# Telecomanda_Licenta.net
KiCad netlist of a schematic drawn in EAGLE
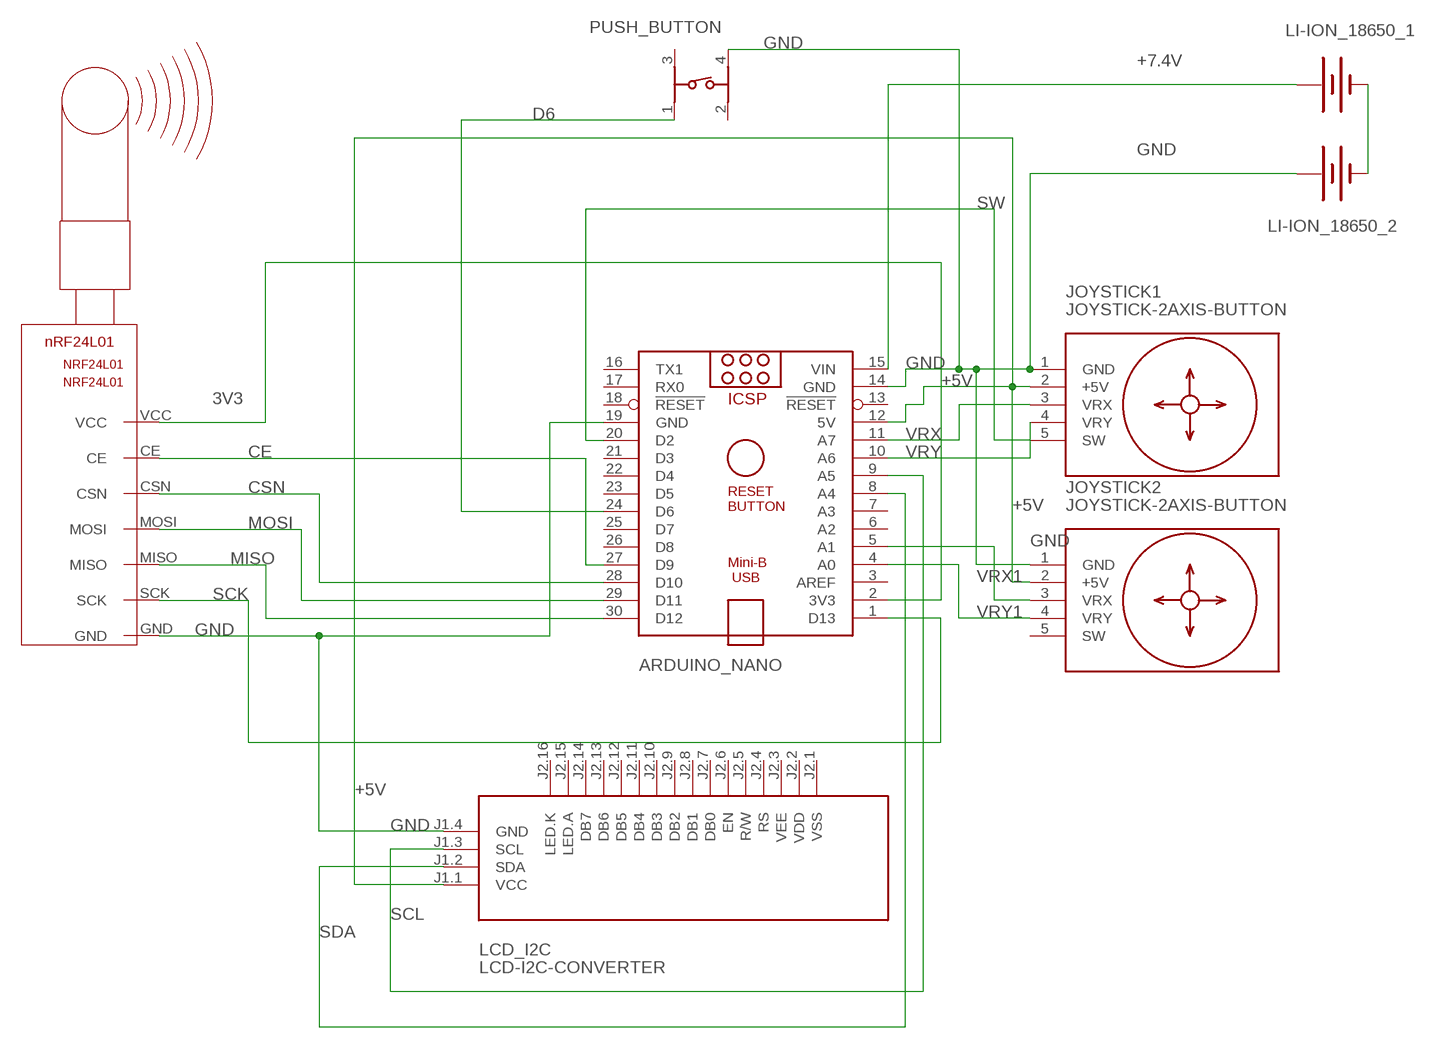
[diagram p0: schematic, sheet 1]

(export (version "E")
  (design (tool "Eeschema 10.0.6"))
  (components
    (comp (ref "ARDUINO_NANO")
      (value "ARDUINO_NANO")
      (footprint "eagle-import:ARDUINO_NANO")
      (libsource (lib "eagle-import") (part "ARDUINO_NANO"))
    )
    (comp (ref "JOYSTICK1")
      (value "JOYSTICK-2AXIS-BUTTON")
      (footprint "eagle-import:JOYSTICK-2AXIS-BUTTON")
      (libsource (lib "eagle-import") (part "JOYSTICK-2AXIS-BUTTON"))
    )
    (comp (ref "JOYSTICK2")
      (value "JOYSTICK-2AXIS-BUTTON")
      (footprint "eagle-import:JOYSTICK-2AXIS-BUTTON")
      (libsource (lib "eagle-import") (part "JOYSTICK-2AXIS-BUTTON"))
    )
    (comp (ref "LCD_I2C")
      (value "LCD-I2C-CONVERTER")
      (footprint "eagle-import:LCD-I2C-CONVERTER")
      (libsource (lib "eagle-import") (part "LCD-I2C-CONVERTER"))
    )
    (comp (ref "LI-ION_18650_1")
      (value "BATTERY-18650")
      (footprint "eagle-import:BATTERY_18650-HOLDER")
      (libsource (lib "eagle-import") (part "BATTERY-18650"))
    )
    (comp (ref "LI-ION_18650_2")
      (value "BATTERY-18650")
      (footprint "eagle-import:BATTERY_18650-HOLDER")
      (libsource (lib "eagle-import") (part "BATTERY-18650"))
    )
    (comp (ref "NRF24L01")
      (value "NRF24L01")
      (footprint "eagle-import:NRF24L01")
      (libsource (lib "eagle-import") (part "NRF24L01"))
    )
    (comp (ref "PUSH_BUTTON")
      (value "430152050836")
      (footprint "eagle-import:430152050836")
      (libsource (lib "eagle-import") (part "430152050836"))
    )
  )
  (nets
    (net (code "1") (name "/+5V") (class "Default")
      (node (ref "ARDUINO_NANO") (pin "12") (pinfunction "5V_12") (pintype "power_in"))
      (node (ref "JOYSTICK1") (pin "2") (pinfunction "+5V_2") (pintype "power_in"))
      (node (ref "JOYSTICK2") (pin "2") (pinfunction "+5V_2") (pintype "power_in"))
      (node (ref "LCD_I2C") (pin "J1.1") (pinfunction "VCC_J1.1") (pintype "power_in"))
    )
    (net (code "2") (name "/+7.4V") (class "Default")
      (node (ref "ARDUINO_NANO") (pin "15") (pinfunction "VIN_15") (pintype "power_in"))
      (node (ref "LI-ION_18650_1") (pin "PWR@1") (pinfunction "+_PWR@1") (pintype "power_in"))
    )
    (net (code "3") (name "/3V3") (class "Default")
      (node (ref "ARDUINO_NANO") (pin "2") (pinfunction "3V3_2") (pintype "output"))
      (node (ref "NRF24L01") (pin "VCC") (pinfunction "VCC_VCC") (pintype "bidirectional"))
    )
    (net (code "4") (name "/CE") (class "Default")
      (node (ref "ARDUINO_NANO") (pin "27") (pinfunction "D9_27") (pintype "bidirectional"))
      (node (ref "NRF24L01") (pin "CE") (pinfunction "CE_CE") (pintype "bidirectional"))
    )
    (net (code "5") (name "/CSN") (class "Default")
      (node (ref "ARDUINO_NANO") (pin "28") (pinfunction "D10_28") (pintype "bidirectional"))
      (node (ref "NRF24L01") (pin "CSN") (pinfunction "CSN_CSN") (pintype "bidirectional"))
    )
    (net (code "6") (name "/D6") (class "Default")
      (node (ref "ARDUINO_NANO") (pin "24") (pinfunction "D6_24") (pintype "bidirectional"))
      (node (ref "PUSH_BUTTON") (pin "1") (pinfunction "1_1") (pintype "passive"))
    )
    (net (code "7") (name "/GND") (class "Default")
      (node (ref "ARDUINO_NANO") (pin "14") (pinfunction "GND_14") (pintype "power_in"))
      (node (ref "ARDUINO_NANO") (pin "19") (pinfunction "GND_19") (pintype "power_in"))
      (node (ref "JOYSTICK1") (pin "1") (pinfunction "GND_1") (pintype "power_in"))
      (node (ref "JOYSTICK2") (pin "1") (pinfunction "GND_1") (pintype "power_in"))
      (node (ref "LCD_I2C") (pin "J1.4") (pinfunction "GND_J1.4") (pintype "power_in"))
      (node (ref "LI-ION_18650_2") (pin "PWR@1") (pinfunction "+_PWR@1") (pintype "power_in"))
      (node (ref "NRF24L01") (pin "GND") (pinfunction "GND_GND") (pintype "bidirectional"))
      (node (ref "PUSH_BUTTON") (pin "4") (pinfunction "4_4") (pintype "passive"))
    )
    (net (code "8") (name "/MISO") (class "Default")
      (node (ref "ARDUINO_NANO") (pin "30") (pinfunction "D12_30") (pintype "bidirectional"))
      (node (ref "NRF24L01") (pin "MISO") (pinfunction "MISO_MISO") (pintype "bidirectional"))
    )
    (net (code "9") (name "/MOSI") (class "Default")
      (node (ref "ARDUINO_NANO") (pin "29") (pinfunction "D11_29") (pintype "bidirectional"))
      (node (ref "NRF24L01") (pin "MOSI") (pinfunction "MOSI_MOSI") (pintype "bidirectional"))
    )
    (net (code "10") (name "/SCK") (class "Default")
      (node (ref "ARDUINO_NANO") (pin "1") (pinfunction "D13_1") (pintype "bidirectional"))
      (node (ref "NRF24L01") (pin "SCK") (pinfunction "SCK_SCK") (pintype "bidirectional"))
    )
    (net (code "11") (name "/SCL") (class "Default")
      (node (ref "ARDUINO_NANO") (pin "9") (pinfunction "A5_9") (pintype "bidirectional"))
      (node (ref "LCD_I2C") (pin "J1.3") (pinfunction "SCL_J1.3") (pintype "bidirectional"))
    )
    (net (code "12") (name "/SDA") (class "Default")
      (node (ref "ARDUINO_NANO") (pin "8") (pinfunction "A4_8") (pintype "bidirectional"))
      (node (ref "LCD_I2C") (pin "J1.2") (pinfunction "SDA_J1.2") (pintype "bidirectional"))
    )
    (net (code "13") (name "/SW") (class "Default")
      (node (ref "ARDUINO_NANO") (pin "20") (pinfunction "D2_20") (pintype "bidirectional"))
      (node (ref "JOYSTICK1") (pin "5") (pinfunction "SW_5") (pintype "passive"))
    )
    (net (code "14") (name "/VRX") (class "Default")
      (node (ref "ARDUINO_NANO") (pin "11") (pinfunction "A7_11") (pintype "bidirectional"))
      (node (ref "JOYSTICK1") (pin "3") (pinfunction "VRX_3") (pintype "passive"))
    )
    (net (code "15") (name "/VRX1") (class "Default")
      (node (ref "ARDUINO_NANO") (pin "5") (pinfunction "A1_5") (pintype "bidirectional"))
      (node (ref "JOYSTICK2") (pin "3") (pinfunction "VRX_3") (pintype "passive"))
    )
    (net (code "16") (name "/VRY") (class "Default")
      (node (ref "ARDUINO_NANO") (pin "10") (pinfunction "A6_10") (pintype "bidirectional"))
      (node (ref "JOYSTICK1") (pin "4") (pinfunction "VRY_4") (pintype "passive"))
    )
    (net (code "17") (name "/VRY1") (class "Default")
      (node (ref "ARDUINO_NANO") (pin "4") (pinfunction "A0_4") (pintype "bidirectional"))
      (node (ref "JOYSTICK2") (pin "4") (pinfunction "VRY_4") (pintype "passive"))
    )
    (net (code "18") (name "Net-(LI-ION_18650_1--)") (class "Default")
      (node (ref "LI-ION_18650_1") (pin "GND@1") (pinfunction "-_GND@1") (pintype "power_in"))
      (node (ref "LI-ION_18650_2") (pin "GND@1") (pinfunction "-_GND@1") (pintype "power_in"))
    )
    (net (code "19") (name "unconnected-(ARDUINO_NANO-A2-Pad6)") (class "Default")
      (node (ref "ARDUINO_NANO") (pin "6") (pinfunction "A2_6") (pintype "bidirectional"))
    )
    (net (code "20") (name "unconnected-(ARDUINO_NANO-A3-Pad7)") (class "Default")
      (node (ref "ARDUINO_NANO") (pin "7") (pinfunction "A3_7") (pintype "bidirectional"))
    )
    (net (code "21") (name "unconnected-(ARDUINO_NANO-AREF-Pad3)") (class "Default")
      (node (ref "ARDUINO_NANO") (pin "3") (pinfunction "AREF_3") (pintype "input"))
    )
    (net (code "22") (name "unconnected-(ARDUINO_NANO-D3-Pad21)") (class "Default")
      (node (ref "ARDUINO_NANO") (pin "21") (pinfunction "D3_21") (pintype "bidirectional"))
    )
    (net (code "23") (name "unconnected-(ARDUINO_NANO-D4-Pad22)") (class "Default")
      (node (ref "ARDUINO_NANO") (pin "22") (pinfunction "D4_22") (pintype "bidirectional"))
    )
    (net (code "24") (name "unconnected-(ARDUINO_NANO-D5-Pad23)") (class "Default")
      (node (ref "ARDUINO_NANO") (pin "23") (pinfunction "D5_23") (pintype "bidirectional"))
    )
    (net (code "25") (name "unconnected-(ARDUINO_NANO-D7-Pad25)") (class "Default")
      (node (ref "ARDUINO_NANO") (pin "25") (pinfunction "D7_25") (pintype "bidirectional"))
    )
    (net (code "26") (name "unconnected-(ARDUINO_NANO-D8-Pad26)") (class "Default")
      (node (ref "ARDUINO_NANO") (pin "26") (pinfunction "D8_26") (pintype "bidirectional"))
    )
    (net (code "27") (name "unconnected-(ARDUINO_NANO-RX0-Pad17)") (class "Default")
      (node (ref "ARDUINO_NANO") (pin "17") (pinfunction "RX0_17") (pintype "bidirectional"))
    )
    (net (code "28") (name "unconnected-(ARDUINO_NANO-TX1-Pad16)") (class "Default")
      (node (ref "ARDUINO_NANO") (pin "16") (pinfunction "TX1_16") (pintype "bidirectional"))
    )
    (net (code "29") (name "unconnected-(ARDUINO_NANO-~{RESET}-Pad13)") (class "Default")
      (node (ref "ARDUINO_NANO") (pin "13") (pinfunction "~{RESET}_13") (pintype "input"))
    )
    (net (code "30") (name "unconnected-(ARDUINO_NANO-~{RESET}-Pad18)") (class "Default")
      (node (ref "ARDUINO_NANO") (pin "18") (pinfunction "~{RESET}_18") (pintype "input"))
    )
    (net (code "31") (name "unconnected-(JOYSTICK2-SW-Pad5)") (class "Default")
      (node (ref "JOYSTICK2") (pin "5") (pinfunction "SW_5") (pintype "passive"))
    )
    (net (code "32") (name "unconnected-(LCD_I2C-DB0-PadJ2.7)") (class "Default")
      (node (ref "LCD_I2C") (pin "J2.7") (pinfunction "DB0_J2.7") (pintype "bidirectional"))
    )
    (net (code "33") (name "unconnected-(LCD_I2C-DB1-PadJ2.8)") (class "Default")
      (node (ref "LCD_I2C") (pin "J2.8") (pinfunction "DB1_J2.8") (pintype "bidirectional"))
    )
    (net (code "34") (name "unconnected-(LCD_I2C-DB2-PadJ2.9)") (class "Default")
      (node (ref "LCD_I2C") (pin "J2.9") (pinfunction "DB2_J2.9") (pintype "bidirectional"))
    )
    (net (code "35") (name "unconnected-(LCD_I2C-DB3-PadJ2.10)") (class "Default")
      (node (ref "LCD_I2C") (pin "J2.10") (pinfunction "DB3_J2.10") (pintype "bidirectional"))
    )
    (net (code "36") (name "unconnected-(LCD_I2C-DB4-PadJ2.11)") (class "Default")
      (node (ref "LCD_I2C") (pin "J2.11") (pinfunction "DB4_J2.11") (pintype "bidirectional"))
    )
    (net (code "37") (name "unconnected-(LCD_I2C-DB5-PadJ2.12)") (class "Default")
      (node (ref "LCD_I2C") (pin "J2.12") (pinfunction "DB5_J2.12") (pintype "bidirectional"))
    )
    (net (code "38") (name "unconnected-(LCD_I2C-DB6-PadJ2.13)") (class "Default")
      (node (ref "LCD_I2C") (pin "J2.13") (pinfunction "DB6_J2.13") (pintype "bidirectional"))
    )
    (net (code "39") (name "unconnected-(LCD_I2C-DB7-PadJ2.14)") (class "Default")
      (node (ref "LCD_I2C") (pin "J2.14") (pinfunction "DB7_J2.14") (pintype "bidirectional"))
    )
    (net (code "40") (name "unconnected-(LCD_I2C-EN-PadJ2.6)") (class "Default")
      (node (ref "LCD_I2C") (pin "J2.6") (pinfunction "EN_J2.6") (pintype "bidirectional"))
    )
    (net (code "41") (name "unconnected-(LCD_I2C-LED.A-PadJ2.15)") (class "Default")
      (node (ref "LCD_I2C") (pin "J2.15") (pinfunction "LED.A_J2.15") (pintype "bidirectional"))
    )
    (net (code "42") (name "unconnected-(LCD_I2C-LED.K-PadJ2.16)") (class "Default")
      (node (ref "LCD_I2C") (pin "J2.16") (pinfunction "LED.K_J2.16") (pintype "bidirectional"))
    )
    (net (code "43") (name "unconnected-(LCD_I2C-RS-PadJ2.4)") (class "Default")
      (node (ref "LCD_I2C") (pin "J2.4") (pinfunction "RS_J2.4") (pintype "bidirectional"))
    )
    (net (code "44") (name "unconnected-(LCD_I2C-R{slash}W-PadJ2.5)") (class "Default")
      (node (ref "LCD_I2C") (pin "J2.5") (pinfunction "R/W_J2.5") (pintype "bidirectional"))
    )
    (net (code "45") (name "unconnected-(LCD_I2C-VDD-PadJ2.2)") (class "Default")
      (node (ref "LCD_I2C") (pin "J2.2") (pinfunction "VDD_J2.2") (pintype "bidirectional"))
    )
    (net (code "46") (name "unconnected-(LCD_I2C-VEE-PadJ2.3)") (class "Default")
      (node (ref "LCD_I2C") (pin "J2.3") (pinfunction "VEE_J2.3") (pintype "bidirectional"))
    )
    (net (code "47") (name "unconnected-(LCD_I2C-VSS-PadJ2.1)") (class "Default")
      (node (ref "LCD_I2C") (pin "J2.1") (pinfunction "VSS_J2.1") (pintype "bidirectional"))
    )
    (net (code "48") (name "unconnected-(PUSH_BUTTON-Pad2)") (class "Default")
      (node (ref "PUSH_BUTTON") (pin "2") (pinfunction "2_2") (pintype "passive"))
    )
    (net (code "49") (name "unconnected-(PUSH_BUTTON-Pad3)") (class "Default")
      (node (ref "PUSH_BUTTON") (pin "3") (pinfunction "3_3") (pintype "passive"))
    )
  )
)
